# PasurV3.net
KiCad netlist of a schematic drawn in EAGLE
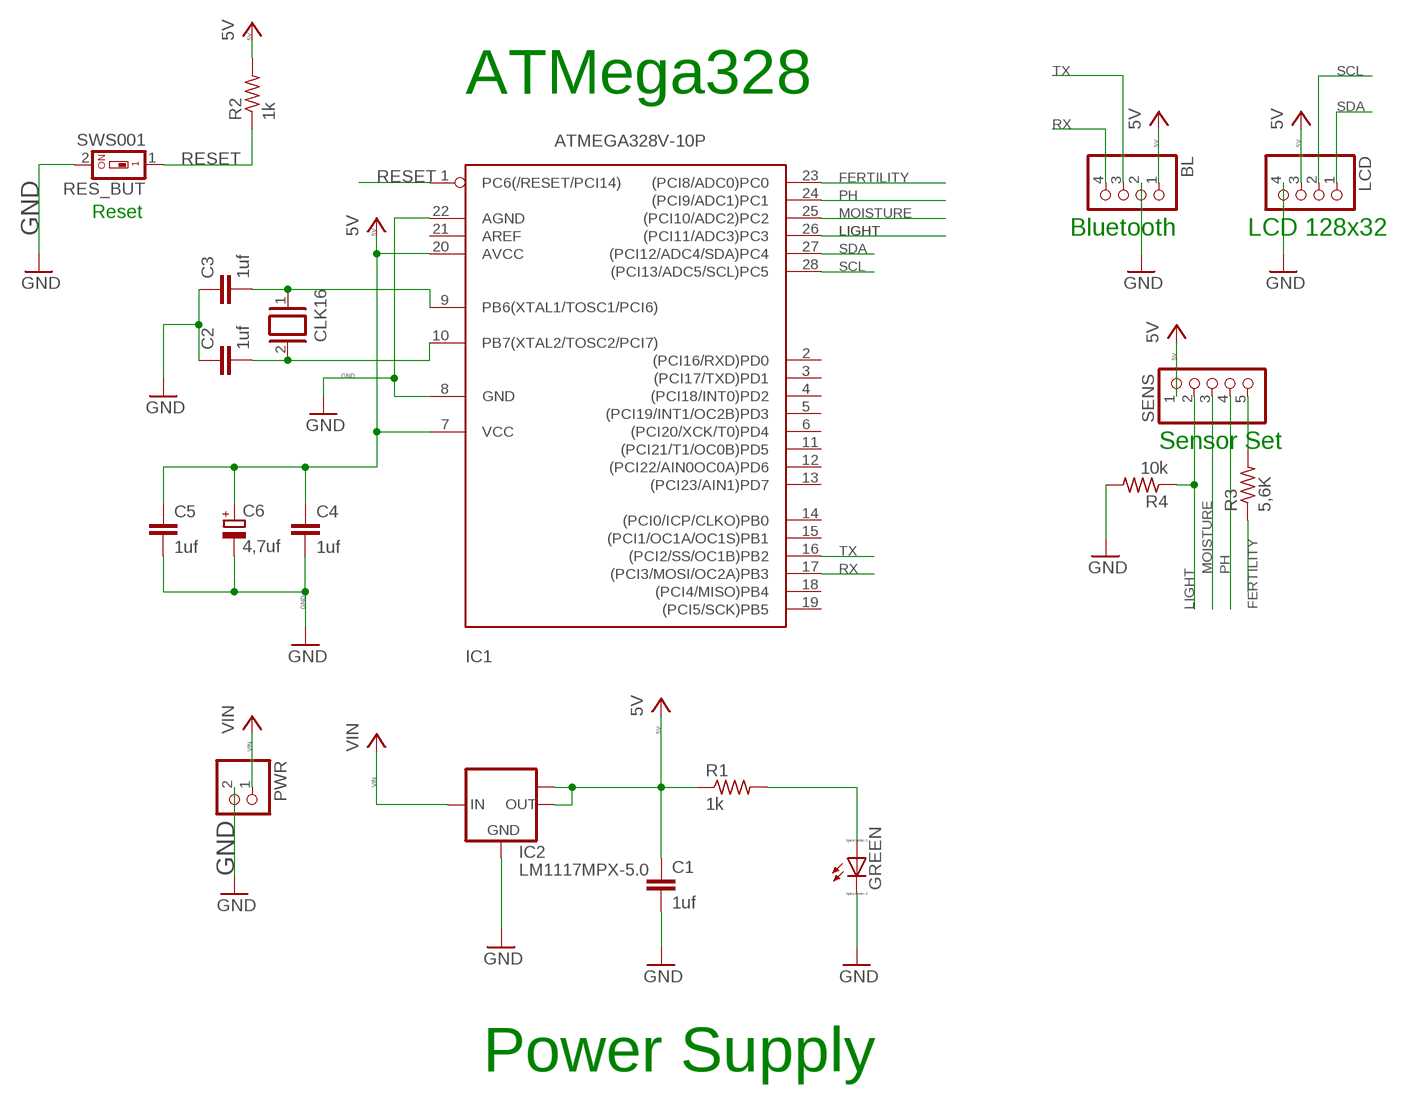
[diagram p0: schematic, sheet 1]

(export (version "E")
  (design (tool "Eeschema 10.0.6"))
  (components
    (comp (ref "BL")
      (value "PINHD-1X4")
      (footprint "eagle-import:1X04")
      (libsource (lib "eagle-import") (part "PINHD-1X4"))
    )
    (comp (ref "C1")
      (value "1uf")
      (footprint "eagle-import:C1206")
      (libsource (lib "eagle-import") (part "C-EUC1206"))
    )
    (comp (ref "C2")
      (value "1uf")
      (footprint "eagle-import:C1206")
      (libsource (lib "eagle-import") (part "C-EUC1206"))
    )
    (comp (ref "C3")
      (value "1uf")
      (footprint "eagle-import:C1206")
      (libsource (lib "eagle-import") (part "C-EUC1206"))
    )
    (comp (ref "C4")
      (value "1uf")
      (footprint "eagle-import:C1206")
      (libsource (lib "eagle-import") (part "C-EUC1206"))
    )
    (comp (ref "C5")
      (value "1uf")
      (footprint "eagle-import:C1206")
      (libsource (lib "eagle-import") (part "C-EUC1206"))
    )
    (comp (ref "C6")
      (value "4,7uf")
      (footprint "eagle-import:A_3216-18W")
      (libsource (lib "eagle-import") (part "CPOL-EUA/3216-18W"))
    )
    (comp (ref "CLK16")
      (value "XTAL/S")
      (footprint "eagle-import:QS")
      (libsource (lib "eagle-import") (part "XTAL/S"))
    )
    (comp (ref "GREEN")
      (value "LED_E")
      (footprint "eagle-import:LED_1206")
      (libsource (lib "eagle-import") (part "LED_E"))
    )
    (comp (ref "IC1")
      (value "ATMEGA328V-10P")
      (footprint "eagle-import:DIL28-3")
      (libsource (lib "eagle-import") (part "ATMEGA328PV-10"))
    )
    (comp (ref "IC2")
      (value "LM1117MPX-5.0")
      (footprint "eagle-import:SOT223")
      (libsource (lib "eagle-import") (part "LM1117MPX-5.0"))
    )
    (comp (ref "LCD")
      (value "PINHD-1X4")
      (footprint "eagle-import:1X04")
      (libsource (lib "eagle-import") (part "PINHD-1X4"))
    )
    (comp (ref "PWR")
      (value "PINHD-1X2")
      (footprint "eagle-import:1X02")
      (libsource (lib "eagle-import") (part "PINHD-1X2"))
    )
    (comp (ref "R1")
      (value "1k")
      (footprint "eagle-import:M1206")
      (libsource (lib "eagle-import") (part "R-US_M1206"))
    )
    (comp (ref "R2")
      (value "1k")
      (footprint "eagle-import:M1206")
      (libsource (lib "eagle-import") (part "R-US_M1206"))
    )
    (comp (ref "R3")
      (value "5,6K")
      (footprint "eagle-import:M1206")
      (libsource (lib "eagle-import") (part "R-US_M1206"))
    )
    (comp (ref "R4")
      (value "10k")
      (footprint "eagle-import:M1206")
      (libsource (lib "eagle-import") (part "R-US_M1206"))
    )
    (comp (ref "RES_BUT")
      (value "SWS001")
      (footprint "eagle-import:SMS-001")
      (libsource (lib "eagle-import") (part "SWS001"))
    )
    (comp (ref "SENS")
      (value "PINHD-1X5")
      (footprint "eagle-import:1X05")
      (libsource (lib "eagle-import") (part "PINHD-1X5"))
    )
  )
  (nets
    (net (code "1") (name "/FERTILITY") (class "Default")
      (node (ref "IC1") (pin "23") (pinfunction "(PCI8/ADC0)PC0_23") (pintype "bidirectional"))
      (node (ref "R3") (pin "1") (pinfunction "1_1") (pintype "passive"))
    )
    (net (code "2") (name "/LIGHT") (class "Default")
      (node (ref "IC1") (pin "26") (pinfunction "(PCI11/ADC3)PC3_26") (pintype "bidirectional"))
      (node (ref "R4") (pin "1") (pinfunction "1_1") (pintype "passive"))
      (node (ref "SENS") (pin "2") (pinfunction "2_2") (pintype "passive"))
    )
    (net (code "3") (name "/MOISTURE") (class "Default")
      (node (ref "IC1") (pin "25") (pinfunction "(PCI10/ADC2)PC2_25") (pintype "bidirectional"))
      (node (ref "SENS") (pin "3") (pinfunction "3_3") (pintype "passive"))
    )
    (net (code "4") (name "/PH") (class "Default")
      (node (ref "IC1") (pin "24") (pinfunction "(PCI9/ADC1)PC1_24") (pintype "bidirectional"))
      (node (ref "SENS") (pin "4") (pinfunction "4_4") (pintype "passive"))
    )
    (net (code "5") (name "/RESET") (class "Default")
      (node (ref "IC1") (pin "1") (pinfunction "PC6(/RESET/PCI14)_1") (pintype "bidirectional"))
      (node (ref "R2") (pin "1") (pinfunction "1_1") (pintype "passive"))
      (node (ref "RES_BUT") (pin "1") (pinfunction "1_1") (pintype "passive"))
    )
    (net (code "6") (name "/RX") (class "Default")
      (node (ref "BL") (pin "4") (pinfunction "4_4") (pintype "passive"))
      (node (ref "IC1") (pin "17") (pinfunction "(PCI3/MOSI/OC2A)PB3_17") (pintype "bidirectional"))
    )
    (net (code "7") (name "/SCL") (class "Default")
      (node (ref "IC1") (pin "28") (pinfunction "(PCI13/ADC5/SCL)PC5_28") (pintype "bidirectional"))
      (node (ref "LCD") (pin "2") (pinfunction "2_2") (pintype "passive"))
    )
    (net (code "8") (name "/SDA") (class "Default")
      (node (ref "IC1") (pin "27") (pinfunction "(PCI12/ADC4/SDA)PC4_27") (pintype "bidirectional"))
      (node (ref "LCD") (pin "1") (pinfunction "1_1") (pintype "passive"))
    )
    (net (code "9") (name "/TX") (class "Default")
      (node (ref "BL") (pin "3") (pinfunction "3_3") (pintype "passive"))
      (node (ref "IC1") (pin "16") (pinfunction "(PCI2/SS/OC1B)PB2_16") (pintype "bidirectional"))
    )
    (net (code "10") (name "5V") (class "Default")
      (node (ref "BL") (pin "1") (pinfunction "1_1") (pintype "passive"))
      (node (ref "C1") (pin "1") (pinfunction "1_1") (pintype "passive"))
      (node (ref "C4") (pin "1") (pinfunction "1_1") (pintype "passive"))
      (node (ref "C5") (pin "1") (pinfunction "1_1") (pintype "passive"))
      (node (ref "C6") (pin "+") (pinfunction "+_+") (pintype "passive"))
      (node (ref "IC1") (pin "20") (pinfunction "AVCC_20") (pintype "bidirectional"))
      (node (ref "IC1") (pin "7") (pinfunction "VCC_7") (pintype "bidirectional"))
      (node (ref "IC2") (pin "2") (pinfunction "OUT_2") (pintype "passive"))
      (node (ref "IC2") (pin "TAB") (pinfunction "OUT1_TAB") (pintype "passive"))
      (node (ref "LCD") (pin "3") (pinfunction "3_3") (pintype "passive"))
      (node (ref "R1") (pin "1") (pinfunction "1_1") (pintype "passive"))
      (node (ref "R2") (pin "2") (pinfunction "2_2") (pintype "passive"))
      (node (ref "SENS") (pin "1") (pinfunction "1_1") (pintype "passive"))
    )
    (net (code "11") (name "GND") (class "Default")
      (node (ref "BL") (pin "2") (pinfunction "2_2") (pintype "passive"))
      (node (ref "C1") (pin "2") (pinfunction "2_2") (pintype "passive"))
      (node (ref "C2") (pin "1") (pinfunction "1_1") (pintype "passive"))
      (node (ref "C3") (pin "1") (pinfunction "1_1") (pintype "passive"))
      (node (ref "C4") (pin "2") (pinfunction "2_2") (pintype "passive"))
      (node (ref "C5") (pin "2") (pinfunction "2_2") (pintype "passive"))
      (node (ref "C6") (pin "-") (pinfunction "-_-") (pintype "passive"))
      (node (ref "GREEN") (pin "C") (pinfunction "C_C") (pintype "passive"))
      (node (ref "IC1") (pin "22") (pinfunction "AGND_22") (pintype "bidirectional"))
      (node (ref "IC1") (pin "8") (pinfunction "GND_8") (pintype "bidirectional"))
      (node (ref "IC2") (pin "1") (pinfunction "GND_1") (pintype "input"))
      (node (ref "LCD") (pin "4") (pinfunction "4_4") (pintype "passive"))
      (node (ref "PWR") (pin "2") (pinfunction "2_2") (pintype "passive"))
      (node (ref "R4") (pin "2") (pinfunction "2_2") (pintype "passive"))
      (node (ref "RES_BUT") (pin "2") (pinfunction "2_2") (pintype "passive"))
    )
    (net (code "12") (name "Net-(GREEN-PadA)") (class "Default")
      (node (ref "GREEN") (pin "A") (pinfunction "A_A") (pintype "passive"))
      (node (ref "R1") (pin "2") (pinfunction "2_2") (pintype "passive"))
    )
    (net (code "13") (name "Net-(IC1-PB6(XTAL1{slash}TOSC1{slash}PCI6))") (class "Default")
      (node (ref "C3") (pin "2") (pinfunction "2_2") (pintype "passive"))
      (node (ref "CLK16") (pin "1") (pinfunction "1_1") (pintype "passive"))
      (node (ref "IC1") (pin "9") (pinfunction "PB6(XTAL1/TOSC1/PCI6)_9") (pintype "bidirectional"))
    )
    (net (code "14") (name "Net-(IC1-PB7(XTAL2{slash}TOSC2{slash}PCI7))") (class "Default")
      (node (ref "C2") (pin "2") (pinfunction "2_2") (pintype "passive"))
      (node (ref "CLK16") (pin "2") (pinfunction "2_2") (pintype "passive"))
      (node (ref "IC1") (pin "10") (pinfunction "PB7(XTAL2/TOSC2/PCI7)_10") (pintype "bidirectional"))
    )
    (net (code "15") (name "Net-(R3-Pad2)") (class "Default")
      (node (ref "R3") (pin "2") (pinfunction "2_2") (pintype "passive"))
      (node (ref "SENS") (pin "5") (pinfunction "5_5") (pintype "passive"))
    )
    (net (code "16") (name "VIN") (class "Default")
      (node (ref "IC2") (pin "3") (pinfunction "IN_3") (pintype "input"))
      (node (ref "PWR") (pin "1") (pinfunction "1_1") (pintype "passive"))
    )
    (net (code "17") (name "unconnected-(IC1-(PCI0{slash}ICP{slash}CLKO)PB0-Pad14)") (class "Default")
      (node (ref "IC1") (pin "14") (pinfunction "(PCI0/ICP/CLKO)PB0_14") (pintype "bidirectional"))
    )
    (net (code "18") (name "unconnected-(IC1-(PCI1{slash}OC1A{slash}OC1S)PB1-Pad15)") (class "Default")
      (node (ref "IC1") (pin "15") (pinfunction "(PCI1/OC1A/OC1S)PB1_15") (pintype "bidirectional"))
    )
    (net (code "19") (name "unconnected-(IC1-(PCI4{slash}MISO)PB4-Pad18)") (class "Default")
      (node (ref "IC1") (pin "18") (pinfunction "(PCI4/MISO)PB4_18") (pintype "bidirectional"))
    )
    (net (code "20") (name "unconnected-(IC1-(PCI5{slash}SCK)PB5-Pad19)") (class "Default")
      (node (ref "IC1") (pin "19") (pinfunction "(PCI5/SCK)PB5_19") (pintype "bidirectional"))
    )
    (net (code "21") (name "unconnected-(IC1-(PCI16{slash}RXD)PD0-Pad2)") (class "Default")
      (node (ref "IC1") (pin "2") (pinfunction "(PCI16/RXD)PD0_2") (pintype "bidirectional"))
    )
    (net (code "22") (name "unconnected-(IC1-(PCI17{slash}TXD)PD1-Pad3)") (class "Default")
      (node (ref "IC1") (pin "3") (pinfunction "(PCI17/TXD)PD1_3") (pintype "bidirectional"))
    )
    (net (code "23") (name "unconnected-(IC1-(PCI18{slash}INT0)PD2-Pad4)") (class "Default")
      (node (ref "IC1") (pin "4") (pinfunction "(PCI18/INT0)PD2_4") (pintype "bidirectional"))
    )
    (net (code "24") (name "unconnected-(IC1-(PCI19{slash}INT1{slash}OC2B)PD3-Pad5)") (class "Default")
      (node (ref "IC1") (pin "5") (pinfunction "(PCI19/INT1/OC2B)PD3_5") (pintype "bidirectional"))
    )
    (net (code "25") (name "unconnected-(IC1-(PCI20{slash}XCK{slash}T0)PD4-Pad6)") (class "Default")
      (node (ref "IC1") (pin "6") (pinfunction "(PCI20/XCK/T0)PD4_6") (pintype "bidirectional"))
    )
    (net (code "26") (name "unconnected-(IC1-(PCI21{slash}T1{slash}OC0B)PD5-Pad11)") (class "Default")
      (node (ref "IC1") (pin "11") (pinfunction "(PCI21/T1/OC0B)PD5_11") (pintype "bidirectional"))
    )
    (net (code "27") (name "unconnected-(IC1-(PCI22{slash}AIN0OC0A)PD6-Pad12)") (class "Default")
      (node (ref "IC1") (pin "12") (pinfunction "(PCI22/AIN0OC0A)PD6_12") (pintype "bidirectional"))
    )
    (net (code "28") (name "unconnected-(IC1-(PCI23{slash}AIN1)PD7-Pad13)") (class "Default")
      (node (ref "IC1") (pin "13") (pinfunction "(PCI23/AIN1)PD7_13") (pintype "bidirectional"))
    )
    (net (code "29") (name "unconnected-(IC1-AREF-Pad21)") (class "Default")
      (node (ref "IC1") (pin "21") (pinfunction "AREF_21") (pintype "bidirectional"))
    )
  )
)
